# PMI_Alim.net
KiCad netlist of a schematic drawn in Altium Designer
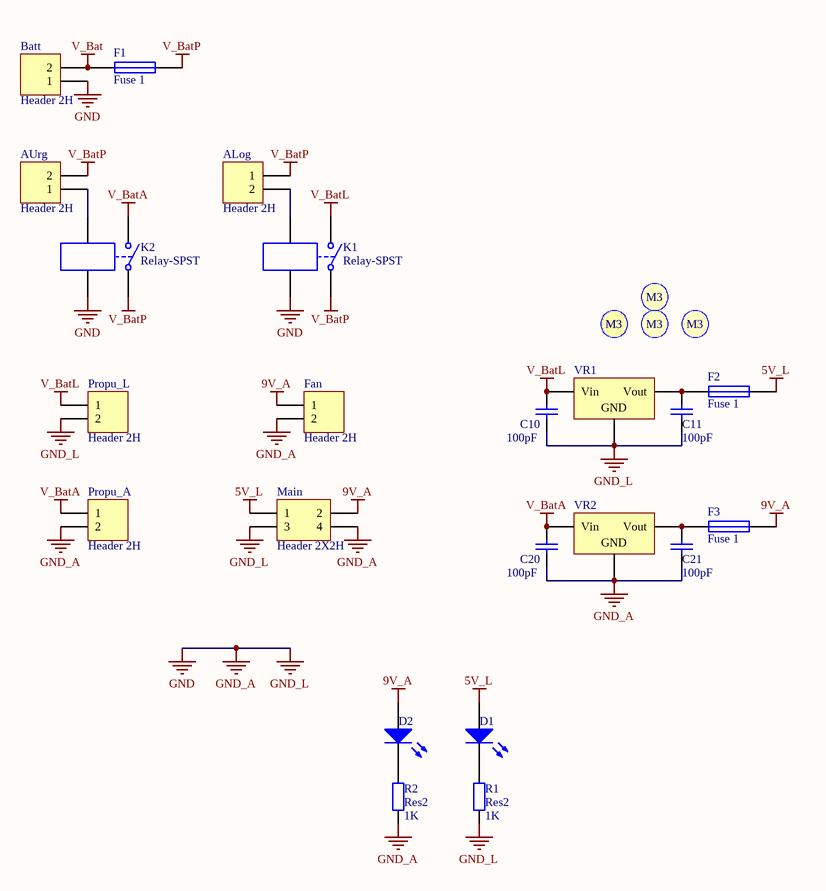
[diagram p0: PMI_Alim.SchDoc]

(export (version "E")
  (design (tool "Eeschema 10.0.6"))
  (components
    (comp (ref "ALog")
      (value "Header 2H")
      (footprint "Molex SPOX 2x1H")
      (description "Header, 2-Pin, Right Angle")
      (fields (field (name "PUBLISHER") "Altium Limited"))
      (libsource (lib "") (part "Header 2H_1"))
    )
    (comp (ref "AUrg")
      (value "Header 2H")
      (footprint "Molex SPOX 2x1H")
      (description "Header, 2-Pin, Right Angle")
      (fields (field (name "PUBLISHER") "Altium Limited"))
      (libsource (lib "") (part "Header 2H_2"))
    )
    (comp (ref "Batt")
      (value "Header 2H")
      (footprint "Battery SALE")
      (description "Header, 2-Pin, Right Angle")
      (fields (field (name "PUBLISHER") "Altium Limited"))
      (libsource (lib "") (part "Header 2H_2"))
    )
    (comp (ref "C10")
      (value "100pF")
      (footprint "3.2X1.6X1.1")
      (description "Capacitor")
      (fields (field (name "Comment") "Cap") (field (name "PUBLISHER") "Altium Limited"))
      (libsource (lib "Miscellaneous Devices") (part "Cap"))
    )
    (comp (ref "C11")
      (value "100pF")
      (footprint "3.2X1.6X1.1")
      (description "Capacitor")
      (fields (field (name "Comment") "Cap") (field (name "PUBLISHER") "Altium Limited"))
      (libsource (lib "Miscellaneous Devices") (part "Cap"))
    )
    (comp (ref "C20")
      (value "100pF")
      (footprint "3.2X1.6X1.1")
      (description "Capacitor")
      (fields (field (name "Comment") "Cap") (field (name "PUBLISHER") "Altium Limited"))
      (libsource (lib "Miscellaneous Devices") (part "Cap"))
    )
    (comp (ref "C21")
      (value "100pF")
      (footprint "3.2X1.6X1.1")
      (description "Capacitor")
      (fields (field (name "Comment") "Cap") (field (name "PUBLISHER") "Altium Limited"))
      (libsource (lib "Miscellaneous Devices") (part "Cap"))
    )
    (comp (ref "D1")
      (value "LED2")
      (footprint "3.2X1.6X1.1")
      (description "Typical RED, GREEN, YELLOW, AMBER GaAs LED")
      (fields (field (name "PUBLISHER") "Altium Limited"))
      (libsource (lib "Miscellaneous Devices") (part "LED2"))
    )
    (comp (ref "D2")
      (value "LED2")
      (footprint "3.2X1.6X1.1")
      (description "Typical RED, GREEN, YELLOW, AMBER GaAs LED")
      (fields (field (name "PUBLISHER") "Altium Limited"))
      (libsource (lib "Miscellaneous Devices") (part "LED2"))
    )
    (comp (ref "F1")
      (value "Fuse 1")
      (footprint "Fuse")
      (description "Fuse")
      (fields (field (name "PUBLISHER") "Altium Limited"))
      (libsource (lib "Miscellaneous Devices") (part "Fuse 1"))
    )
    (comp (ref "F2")
      (value "Fuse 1")
      (footprint "Fuse")
      (description "Fuse")
      (fields (field (name "PUBLISHER") "Altium Limited"))
      (libsource (lib "Miscellaneous Devices") (part "Fuse 1"))
    )
    (comp (ref "F3")
      (value "Fuse 1")
      (footprint "Fuse")
      (description "Fuse")
      (fields (field (name "PUBLISHER") "Altium Limited"))
      (libsource (lib "Miscellaneous Devices") (part "Fuse 1"))
    )
    (comp (ref "Fan")
      (value "Header 2H")
      (footprint "Molex SPOX 2x1H")
      (description "Header, 2-Pin, Right Angle")
      (fields (field (name "PUBLISHER") "Altium Limited"))
      (libsource (lib "Miscellaneous Connectors") (part "Header 2H"))
    )
    (comp (ref "K1")
      (value "Relay-SPST")
      (footprint "Relay")
      (description "Single-Pole Single-Throw Relay")
      (fields (field (name "PUBLISHER") "Altium Limited"))
      (libsource (lib "Miscellaneous Devices") (part "Relay-SPST"))
    )
    (comp (ref "K2")
      (value "Relay-SPST")
      (footprint "Relay")
      (description "Single-Pole Single-Throw Relay")
      (fields (field (name "PUBLISHER") "Altium Limited"))
      (libsource (lib "Miscellaneous Devices") (part "Relay-SPST"))
    )
    (comp (ref "Main")
      (value "Header 2X2H")
      (footprint "MOLEX_MINIFITJR_2X2H")
      (description "Header, 2-Pin, Dual row, Right Angle")
      (fields (field (name "PUBLISHER") "Altium Limited"))
      (libsource (lib "Miscellaneous Connectors") (part "Header 2X2H"))
    )
    (comp (ref "Propu_A")
      (value "Header 2H")
      (footprint "Molex_MiniFitJr_2x1H")
      (description "Header, 2-Pin, Right Angle")
      (fields (field (name "PUBLISHER") "Altium Limited"))
      (libsource (lib "Miscellaneous Connectors") (part "Header 2H"))
    )
    (comp (ref "Propu_L")
      (value "Header 2H")
      (footprint "Molex_MiniFitJr_2x1H")
      (description "Header, 2-Pin, Right Angle")
      (fields (field (name "PUBLISHER") "Altium Limited"))
      (libsource (lib "Miscellaneous Connectors") (part "Header 2H"))
    )
    (comp (ref "R1")
      (value "Res2")
      (footprint "3.2X1.6X1.1")
      (description "Resistor")
      (fields (field (name "ALTIUM_VALUE") "1K") (field (name "PUBLISHER") "Altium Limited"))
      (libsource (lib "Miscellaneous Devices") (part "Res2"))
    )
    (comp (ref "R2")
      (value "Res2")
      (footprint "3.2X1.6X1.1")
      (description "Resistor")
      (fields (field (name "ALTIUM_VALUE") "1K") (field (name "PUBLISHER") "Altium Limited"))
      (libsource (lib "Miscellaneous Devices") (part "Res2"))
    )
    (comp (ref "S1")
      (value "Screw M3")
      (footprint "Robot_2019:Screw M3")
      (libsource (lib "Robot_2019") (part "Screw M3"))
    )
    (comp (ref "S2")
      (value "Screw M3")
      (footprint "Robot_2019:Screw M3")
      (libsource (lib "Robot_2019") (part "Screw M3"))
    )
    (comp (ref "S3")
      (value "Screw M3")
      (footprint "Robot_2019:Screw M3")
      (libsource (lib "Robot_2019") (part "Screw M3"))
    )
    (comp (ref "S4")
      (value "Screw M3")
      (footprint "Robot_2019:Screw M3")
      (libsource (lib "Robot_2019") (part "Screw M3"))
    )
    (comp (ref "S5")
      (value "Screw M3")
      (footprint "Robot_2019:Screw M3")
      (libsource (lib "Robot_2019") (part "Screw M3"))
    )
    (comp (ref "VR1")
      (value "TSR 2-2450")
      (footprint "TRS - centered")
      (description "Voltage Regulator")
      (fields (field (name "PUBLISHER") "Altium Limited"))
      (libsource (lib "Miscellaneous Devices") (part "Volt Reg"))
    )
    (comp (ref "VR2")
      (value "TSR 2-2490")
      (footprint "TRS - centered")
      (description "Voltage Regulator")
      (fields (field (name "PUBLISHER") "Altium Limited"))
      (libsource (lib "Miscellaneous Devices") (part "Volt Reg"))
    )
  )
  (nets
    (net (code "1") (name "5V_L") (class "Default")
      (node (ref "D1") (pin "1") (pinfunction "A_1") (pintype "passive"))
      (node (ref "F2") (pin "2") (pinfunction "2_2") (pintype "passive"))
      (node (ref "Main") (pin "1") (pinfunction "1_1") (pintype "passive"))
    )
    (net (code "2") (name "9V_A") (class "Default")
      (node (ref "D2") (pin "1") (pinfunction "A_1") (pintype "passive"))
      (node (ref "F3") (pin "2") (pinfunction "2_2") (pintype "passive"))
      (node (ref "Fan") (pin "1") (pinfunction "1_1") (pintype "passive"))
      (node (ref "Main") (pin "2") (pinfunction "2_2") (pintype "passive"))
    )
    (net (code "3") (name "GND") (class "Default")
      (node (ref "Batt") (pin "1") (pinfunction "1_1") (pintype "passive"))
      (node (ref "C10") (pin "1") (pinfunction "1_1") (pintype "passive"))
      (node (ref "C11") (pin "1") (pinfunction "1_1") (pintype "passive"))
      (node (ref "C20") (pin "1") (pinfunction "1_1") (pintype "passive"))
      (node (ref "C21") (pin "1") (pinfunction "1_1") (pintype "passive"))
      (node (ref "Fan") (pin "2") (pinfunction "2_2") (pintype "passive"))
      (node (ref "K1") (pin "3") (pinfunction "3_3") (pintype "passive"))
      (node (ref "K2") (pin "3") (pinfunction "3_3") (pintype "passive"))
      (node (ref "Main") (pin "3") (pinfunction "3_3") (pintype "passive"))
      (node (ref "Main") (pin "4") (pinfunction "4_4") (pintype "passive"))
      (node (ref "Propu_A") (pin "2") (pinfunction "2_2") (pintype "passive"))
      (node (ref "Propu_L") (pin "2") (pinfunction "2_2") (pintype "passive"))
      (node (ref "R1") (pin "2") (pinfunction "2_2") (pintype "passive"))
      (node (ref "R2") (pin "2") (pinfunction "2_2") (pintype "passive"))
      (node (ref "VR1") (pin "2") (pinfunction "GND_2") (pintype "passive"))
      (node (ref "VR2") (pin "2") (pinfunction "GND_2") (pintype "passive"))
    )
    (net (code "4") (name "Net-(ALog-Pad2)") (class "Default")
      (node (ref "ALog") (pin "2") (pinfunction "2_2") (pintype "passive"))
      (node (ref "K1") (pin "4") (pinfunction "4_4") (pintype "passive"))
    )
    (net (code "5") (name "Net-(AUrg-Pad1)") (class "Default")
      (node (ref "AUrg") (pin "1") (pinfunction "1_1") (pintype "passive"))
      (node (ref "K2") (pin "4") (pinfunction "4_4") (pintype "passive"))
    )
    (net (code "6") (name "Net-(D1-K)") (class "Default")
      (node (ref "D1") (pin "2") (pinfunction "K_2") (pintype "passive"))
      (node (ref "R1") (pin "1") (pinfunction "1_1") (pintype "passive"))
    )
    (net (code "7") (name "Net-(D2-K)") (class "Default")
      (node (ref "D2") (pin "2") (pinfunction "K_2") (pintype "passive"))
      (node (ref "R2") (pin "1") (pinfunction "1_1") (pintype "passive"))
    )
    (net (code "8") (name "Net-(VR1-Vout)") (class "Default")
      (node (ref "C11") (pin "2") (pinfunction "2_2") (pintype "passive"))
      (node (ref "F2") (pin "1") (pinfunction "1_1") (pintype "passive"))
      (node (ref "VR1") (pin "3") (pinfunction "Vout_3") (pintype "passive"))
    )
    (net (code "9") (name "Net-(VR2-Vout)") (class "Default")
      (node (ref "C21") (pin "2") (pinfunction "2_2") (pintype "passive"))
      (node (ref "F3") (pin "1") (pinfunction "1_1") (pintype "passive"))
      (node (ref "VR2") (pin "3") (pinfunction "Vout_3") (pintype "passive"))
    )
    (net (code "10") (name "V_Bat") (class "Default")
      (node (ref "Batt") (pin "2") (pinfunction "2_2") (pintype "passive"))
      (node (ref "F1") (pin "1") (pinfunction "1_1") (pintype "passive"))
    )
    (net (code "11") (name "V_BatA") (class "Default")
      (node (ref "C20") (pin "2") (pinfunction "2_2") (pintype "passive"))
      (node (ref "K2") (pin "2") (pinfunction "2_2") (pintype "passive"))
      (node (ref "Propu_A") (pin "1") (pinfunction "1_1") (pintype "passive"))
      (node (ref "VR2") (pin "1") (pinfunction "Vin_1") (pintype "passive"))
    )
    (net (code "12") (name "V_BatL") (class "Default")
      (node (ref "C10") (pin "2") (pinfunction "2_2") (pintype "passive"))
      (node (ref "K1") (pin "2") (pinfunction "2_2") (pintype "passive"))
      (node (ref "Propu_L") (pin "1") (pinfunction "1_1") (pintype "passive"))
      (node (ref "VR1") (pin "1") (pinfunction "Vin_1") (pintype "passive"))
    )
    (net (code "13") (name "V_BatP") (class "Default")
      (node (ref "ALog") (pin "1") (pinfunction "1_1") (pintype "passive"))
      (node (ref "AUrg") (pin "2") (pinfunction "2_2") (pintype "passive"))
      (node (ref "F1") (pin "2") (pinfunction "2_2") (pintype "passive"))
      (node (ref "K1") (pin "1") (pinfunction "1_1") (pintype "passive"))
      (node (ref "K2") (pin "1") (pinfunction "1_1") (pintype "passive"))
    )
  )
)
